# RX-FM-One-Transistor-Super-Regen.net
KiCad netlist of a schematic drawn in EAGLE
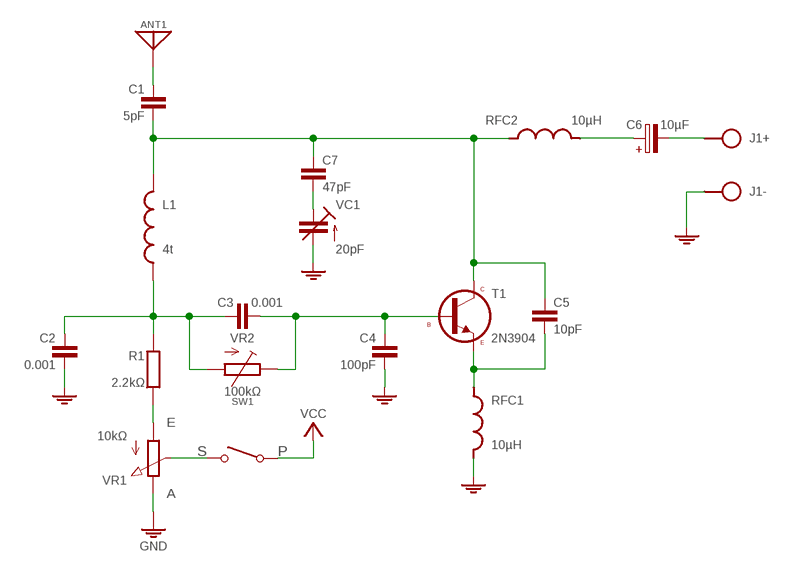
[diagram p0: schematic, sheet 1]

(export (version "E")
  (design (tool "Eeschema 10.0.6"))
  (components
    (comp (ref "ANT1")
      (value "ANT")
      (footprint "eagle-import:SPAD")
      (libsource (lib "eagle-import") (part "ANT"))
    )
    (comp (ref "C1")
      (value "5pF")
      (footprint "eagle-import:C025-015X024")
      (libsource (lib "eagle-import") (part "C025-015X024"))
    )
    (comp (ref "C2")
      (value "0.001")
      (footprint "eagle-import:C050-020X036_V")
      (libsource (lib "eagle-import") (part "C050-020X036/V"))
    )
    (comp (ref "C3")
      (value "0.001")
      (footprint "eagle-import:C050-020X036")
      (libsource (lib "eagle-import") (part "C-H050-020X036"))
    )
    (comp (ref "C4")
      (value "100pF")
      (footprint "eagle-import:C050-020X036_V")
      (libsource (lib "eagle-import") (part "C050-020X036/V"))
    )
    (comp (ref "C5")
      (value "10pF")
      (footprint "eagle-import:C050-020X036_V")
      (libsource (lib "eagle-import") (part "C050-020X036/V"))
    )
    (comp (ref "C6")
      (value "10µF")
      (footprint "eagle-import:E2,5-4")
      (libsource (lib "eagle-import") (part "CPOL-HE2,5-4"))
    )
    (comp (ref "C7")
      (value "47pF")
      (footprint "eagle-import:C025-015X024")
      (libsource (lib "eagle-import") (part "C025-015X024"))
    )
    (comp (ref "J1")
      (value "SPAD+-+-")
      (footprint "eagle-import:SPAD+-")
      (libsource (lib "eagle-import") (part "SPAD+-+-"))
    )
    (comp (ref "L1")
      (value "4t")
      (footprint "eagle-import:L-04_7-V")
      (libsource (lib "eagle-import") (part "L04/7-V"))
    )
    (comp (ref "R1")
      (value "2.2kΩ")
      (footprint "eagle-import:0204_10-V")
      (libsource (lib "eagle-import") (part "R0204/10-V"))
    )
    (comp (ref "RFC1")
      (value "10µH")
      (footprint "eagle-import:L-04-2_5V")
      (libsource (lib "eagle-import") (part "L-SHORT04-2/5V"))
    )
    (comp (ref "RFC2")
      (value "10µH")
      (footprint "eagle-import:L-03_10")
      (libsource (lib "eagle-import") (part "L-H-SHORT-03/10"))
    )
    (comp (ref "S6")
      (value "VCC_GNDPWR-R")
      (footprint "eagle-import:PWR-R")
      (libsource (lib "eagle-import") (part "VCC_GNDPWR-R"))
    )
    (comp (ref "SW1")
      (value "SW-SPST-SL-1P2T-H")
      (footprint "eagle-import:SLSW-1P2T-H")
      (libsource (lib "eagle-import") (part "SW-SPST-SL-1P2T-H"))
    )
    (comp (ref "T1")
      (value "2N3904")
      (footprint "eagle-import:TO92")
      (libsource (lib "eagle-import") (part "2N3904"))
    )
    (comp (ref "VC1")
      (value "20pF")
      (footprint "eagle-import:TRIM-2222-808")
      (libsource (lib "eagle-import") (part "C-TR-PH20127"))
    )
    (comp (ref "VR1")
      (value "10kΩ")
      (footprint "eagle-import:TRIM-POT")
      (libsource (lib "eagle-import") (part "POT-TRIM"))
    )
    (comp (ref "VR2")
      (value "100kΩ")
      (footprint "eagle-import:TRIM-POT")
      (libsource (lib "eagle-import") (part "TRIM-2-TR-3TO2"))
    )
  )
  (nets
    (net (code "1") (name "GND") (class "Default")
      (node (ref "C2") (pin "2") (pinfunction "2_2") (pintype "passive"))
      (node (ref "C4") (pin "2") (pinfunction "2_2") (pintype "passive"))
      (node (ref "J1") (pin "1") (pinfunction "P$1_1") (pintype "passive"))
      (node (ref "RFC1") (pin "1") (pinfunction "1_1") (pintype "passive"))
      (node (ref "S6") (pin "1") (pinfunction "GND_1") (pintype "power_in"))
      (node (ref "VC1") (pin "1") (pinfunction "A_1") (pintype "passive"))
      (node (ref "VC1") (pin "3") (pinfunction "A_3") (pintype "passive"))
      (node (ref "VR1") (pin "E") (pinfunction "E_E") (pintype "passive"))
    )
    (net (code "2") (name "Net-(ANT1-Pad1)") (class "Default")
      (node (ref "ANT1") (pin "1") (pinfunction "1_1") (pintype "output"))
      (node (ref "C1") (pin "1") (pinfunction "1_1") (pintype "passive"))
    )
    (net (code "3") (name "Net-(C6-Pad+)") (class "Default")
      (node (ref "C6") (pin "+") (pinfunction "+_+") (pintype "passive"))
      (node (ref "RFC2") (pin "1") (pinfunction "1_1") (pintype "passive"))
    )
    (net (code "4") (name "Net-(J1A-P$1)") (class "Default")
      (node (ref "C6") (pin "-") (pinfunction "-_-") (pintype "passive"))
      (node (ref "J1") (pin "2") (pinfunction "P$1_2") (pintype "passive"))
    )
    (net (code "5") (name "Net-(R1-1)") (class "Default")
      (node (ref "R1") (pin "2") (pinfunction "1_2") (pintype "passive"))
      (node (ref "VR1") (pin "A") (pinfunction "A_A") (pintype "passive"))
    )
    (net (code "6") (name "Net-(R1-2)") (class "Default")
      (node (ref "C2") (pin "1") (pinfunction "1_1") (pintype "passive"))
      (node (ref "C3") (pin "1") (pinfunction "1_1") (pintype "passive"))
      (node (ref "L1") (pin "2") (pinfunction "2_2") (pintype "passive"))
      (node (ref "R1") (pin "1") (pinfunction "2_1") (pintype "passive"))
      (node (ref "VR2") (pin "E") (pinfunction "2_E") (pintype "passive"))
      (node (ref "VR2") (pin "S") (pinfunction "2_S") (pintype "passive"))
    )
    (net (code "7") (name "Net-(S6A-VCC)") (class "Default")
      (node (ref "S6") (pin "2") (pinfunction "VCC_2") (pintype "power_in"))
      (node (ref "SW1") (pin "P") (pinfunction "P_P") (pintype "passive"))
    )
    (net (code "8") (name "Net-(SW1-PadS)") (class "Default")
      (node (ref "SW1") (pin "S") (pinfunction "S_S") (pintype "passive"))
      (node (ref "VR1") (pin "S") (pinfunction "S_S") (pintype "passive"))
    )
    (net (code "9") (name "Net-(T1-B)") (class "Default")
      (node (ref "C3") (pin "2") (pinfunction "2_2") (pintype "passive"))
      (node (ref "C4") (pin "1") (pinfunction "1_1") (pintype "passive"))
      (node (ref "T1") (pin "2") (pinfunction "B_2") (pintype "passive"))
      (node (ref "VR2") (pin "A") (pinfunction "1_A") (pintype "passive"))
    )
    (net (code "10") (name "Net-(T1-C)") (class "Default")
      (node (ref "C1") (pin "2") (pinfunction "2_2") (pintype "passive"))
      (node (ref "C5") (pin "1") (pinfunction "1_1") (pintype "passive"))
      (node (ref "C7") (pin "1") (pinfunction "1_1") (pintype "passive"))
      (node (ref "L1") (pin "1") (pinfunction "1_1") (pintype "passive"))
      (node (ref "RFC2") (pin "2") (pinfunction "2_2") (pintype "passive"))
      (node (ref "T1") (pin "3") (pinfunction "C_3") (pintype "passive"))
    )
    (net (code "11") (name "Net-(T1-E)") (class "Default")
      (node (ref "C5") (pin "2") (pinfunction "2_2") (pintype "passive"))
      (node (ref "RFC1") (pin "2") (pinfunction "2_2") (pintype "passive"))
      (node (ref "T1") (pin "1") (pinfunction "E_1") (pintype "passive"))
    )
    (net (code "12") (name "Net-(VC1-E)") (class "Default")
      (node (ref "C7") (pin "2") (pinfunction "2_2") (pintype "passive"))
      (node (ref "VC1") (pin "2") (pinfunction "E_2") (pintype "passive"))
    )
  )
)
